# vusbtinyisp_through-hole.net
KiCad netlist of a schematic drawn in EAGLE
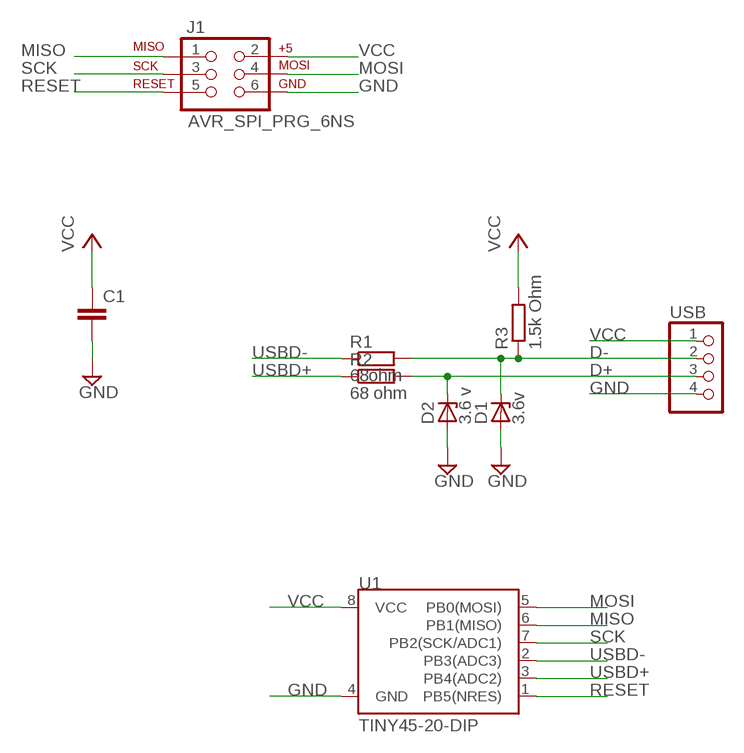
[diagram p0: schematic, sheet 1]

(export (version "E")
  (design (tool "Eeschema 10.0.6"))
  (components
    (comp (ref "C1")
      (value "CAPPTH")
      (footprint "eagle-import:CAP-PTH-SMALL")
      (libsource (lib "eagle-import") (part "CAPPTH"))
    )
    (comp (ref "D1")
      (value "3.6v")
      (footprint "eagle-import:DO35Z10")
      (libsource (lib "eagle-import") (part "ZENER-DIODEDO35Z10"))
    )
    (comp (ref "D2")
      (value "3.6 v")
      (footprint "eagle-import:DO35Z10")
      (libsource (lib "eagle-import") (part "ZENER-DIODEDO35Z10"))
    )
    (comp (ref "J1")
      (value "AVR_SPI_PRG_6NS")
      (footprint "eagle-import:2X3-NS")
      (libsource (lib "eagle-import") (part "AVR_SPI_PRG_6NS"))
    )
    (comp (ref "R1")
      (value "68ohm")
      (footprint "eagle-import:0207_10")
      (libsource (lib "eagle-import") (part "R-EU_0207/10"))
    )
    (comp (ref "R2")
      (value "68 ohm")
      (footprint "eagle-import:0207_10")
      (libsource (lib "eagle-import") (part "R-EU_0207/10"))
    )
    (comp (ref "R3")
      (value "1.5k Ohm")
      (footprint "eagle-import:0207_10")
      (libsource (lib "eagle-import") (part "R-EU_0207/10"))
    )
    (comp (ref "U1")
      (value "TINY45-20-DIP")
      (footprint "eagle-import:DIP08")
      (libsource (lib "eagle-import") (part "ATTINY45TINY45-20-DIP"))
    )
    (comp (ref "USB")
      (value "PINHD-1X4")
      (footprint "eagle-import:1X04")
      (libsource (lib "eagle-import") (part "PINHD-1X4"))
    )
  )
  (nets
    (net (code "1") (name "/D+") (class "Default")
      (node (ref "D2") (pin "C") (pinfunction "C_C") (pintype "passive"))
      (node (ref "R2") (pin "2") (pinfunction "2_2") (pintype "passive"))
      (node (ref "USB") (pin "3") (pinfunction "3_3") (pintype "passive"))
    )
    (net (code "2") (name "/D-") (class "Default")
      (node (ref "D1") (pin "C") (pinfunction "C_C") (pintype "passive"))
      (node (ref "R1") (pin "2") (pinfunction "2_2") (pintype "passive"))
      (node (ref "R3") (pin "1") (pinfunction "1_1") (pintype "passive"))
      (node (ref "USB") (pin "2") (pinfunction "2_2") (pintype "passive"))
    )
    (net (code "3") (name "/MISO") (class "Default")
      (node (ref "J1") (pin "1") (pinfunction "1_1") (pintype "passive"))
      (node (ref "U1") (pin "6") (pinfunction "PB1(MISO)_6") (pintype "bidirectional"))
    )
    (net (code "4") (name "/MOSI") (class "Default")
      (node (ref "J1") (pin "4") (pinfunction "4_4") (pintype "passive"))
      (node (ref "U1") (pin "5") (pinfunction "PB0(MOSI)_5") (pintype "bidirectional"))
    )
    (net (code "5") (name "/RESET") (class "Default")
      (node (ref "J1") (pin "5") (pinfunction "5_5") (pintype "passive"))
      (node (ref "U1") (pin "1") (pinfunction "PB5(NRES)_1") (pintype "bidirectional"))
    )
    (net (code "6") (name "/SCK") (class "Default")
      (node (ref "J1") (pin "3") (pinfunction "3_3") (pintype "passive"))
      (node (ref "U1") (pin "7") (pinfunction "PB2(SCK/ADC1)_7") (pintype "bidirectional"))
    )
    (net (code "7") (name "/USBD+") (class "Default")
      (node (ref "R2") (pin "1") (pinfunction "1_1") (pintype "passive"))
      (node (ref "U1") (pin "3") (pinfunction "PB4(ADC2)_3") (pintype "bidirectional"))
    )
    (net (code "8") (name "/USBD-") (class "Default")
      (node (ref "R1") (pin "1") (pinfunction "1_1") (pintype "passive"))
      (node (ref "U1") (pin "2") (pinfunction "PB3(ADC3)_2") (pintype "bidirectional"))
    )
    (net (code "9") (name "GND") (class "Default")
      (node (ref "C1") (pin "2") (pinfunction "2_2") (pintype "passive"))
      (node (ref "D1") (pin "A") (pinfunction "A_A") (pintype "passive"))
      (node (ref "D2") (pin "A") (pinfunction "A_A") (pintype "passive"))
      (node (ref "J1") (pin "6") (pinfunction "6_6") (pintype "passive"))
      (node (ref "U1") (pin "4") (pinfunction "GND_4") (pintype "bidirectional"))
      (node (ref "USB") (pin "4") (pinfunction "4_4") (pintype "passive"))
    )
    (net (code "10") (name "VCC") (class "Default")
      (node (ref "C1") (pin "1") (pinfunction "1_1") (pintype "passive"))
      (node (ref "J1") (pin "2") (pinfunction "2_2") (pintype "passive"))
      (node (ref "R3") (pin "2") (pinfunction "2_2") (pintype "passive"))
      (node (ref "U1") (pin "8") (pinfunction "VCC_8") (pintype "bidirectional"))
      (node (ref "USB") (pin "1") (pinfunction "1_1") (pintype "passive"))
    )
  )
)
